# servo_header_board.net
KiCad netlist of a schematic drawn in Altium Designer
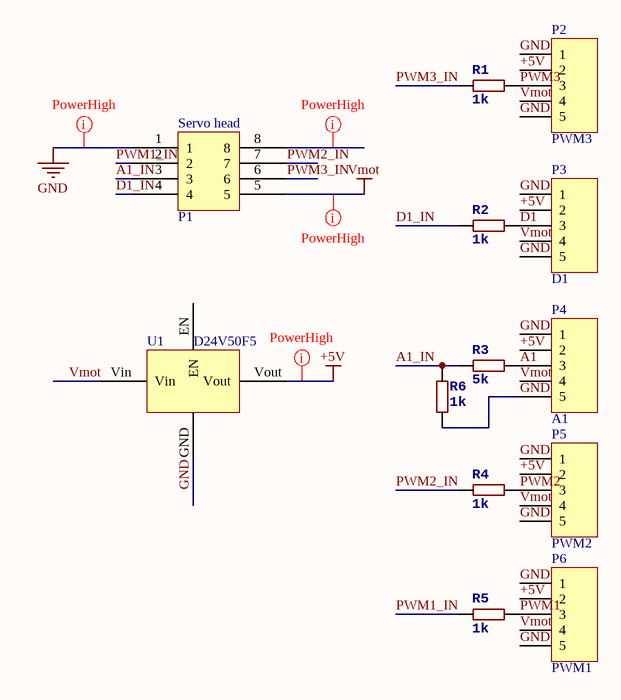
[diagram p0: servo_header_board.SchDoc]

(export (version "E")
  (design (tool "Eeschema 10.0.6"))
  (components
    (comp (ref "P1")
      (value "Servo head")
      (footprint "HOUSED8")
      (libsource (lib "myParts") (part "PIN_HOUSED_8"))
    )
    (comp (ref "P2")
      (value "PWM3")
      (footprint "HDR1X5")
      (description "Header, 5-Pin")
      (fields (field (name "PUBLISHER") "Altium Limited"))
      (libsource (lib "Miscellaneous Connectors") (part "Header 5"))
    )
    (comp (ref "P3")
      (value "D1")
      (footprint "HDR1X5")
      (description "Header, 5-Pin")
      (fields (field (name "PUBLISHER") "Altium Limited"))
      (libsource (lib "Miscellaneous Connectors") (part "Header 5"))
    )
    (comp (ref "P4")
      (value "A1")
      (footprint "HDR1X5")
      (description "Header, 5-Pin")
      (fields (field (name "PUBLISHER") "Altium Limited"))
      (libsource (lib "Miscellaneous Connectors") (part "Header 5"))
    )
    (comp (ref "P5")
      (value "PWM2")
      (footprint "HDR1X5")
      (description "Header, 5-Pin")
      (fields (field (name "PUBLISHER") "Altium Limited"))
      (libsource (lib "Miscellaneous Connectors") (part "Header 5"))
    )
    (comp (ref "P6")
      (value "PWM1")
      (footprint "HDR1X5")
      (description "Header, 5-Pin")
      (fields (field (name "PUBLISHER") "Altium Limited"))
      (libsource (lib "Miscellaneous Connectors") (part "Header 5"))
    )
    (comp (ref "R1")
      (value "1k")
      (footprint "R0805")
      (description "RESISTOR, European symbol")
      (libsource (lib "rcl") (part "R-EU"))
    )
    (comp (ref "R2")
      (value "1k")
      (footprint "R0805")
      (description "RESISTOR, European symbol")
      (libsource (lib "rcl") (part "R-EU"))
    )
    (comp (ref "R3")
      (value "5k")
      (footprint "R0805")
      (description "RESISTOR, European symbol")
      (libsource (lib "rcl") (part "R-EU"))
    )
    (comp (ref "R4")
      (value "1k")
      (footprint "R0805")
      (description "RESISTOR, European symbol")
      (libsource (lib "rcl") (part "R-EU"))
    )
    (comp (ref "R5")
      (value "1k")
      (footprint "R0805")
      (description "RESISTOR, European symbol")
      (libsource (lib "rcl") (part "R-EU"))
    )
    (comp (ref "R6")
      (value "1k")
      (footprint "R0805")
      (description "RESISTOR, European symbol")
      (libsource (lib "rcl") (part "R-EU"))
    )
    (comp (ref "U1")
      (value "D24V50F5")
      (footprint "D24V50F5-hori")
      (description "Pololu 5V, 5A Step-Down Voltage Regulator")
      (libsource (lib "myParts") (part "D24V50F5"))
    )
  )
  (nets
    (net (code "1") (name "+5V") (class "Default")
      (node (ref "P2") (pin "2") (pinfunction "2_2") (pintype "passive"))
      (node (ref "P3") (pin "2") (pinfunction "2_2") (pintype "passive"))
      (node (ref "P4") (pin "2") (pinfunction "2_2") (pintype "passive"))
      (node (ref "P5") (pin "2") (pinfunction "2_2") (pintype "passive"))
      (node (ref "P6") (pin "2") (pinfunction "2_2") (pintype "passive"))
      (node (ref "U1") (pin "Vout") (pinfunction "Vout_Vout") (pintype "power_in"))
    )
    (net (code "2") (name "/A1") (class "Default")
      (node (ref "P4") (pin "3") (pinfunction "3_3") (pintype "passive"))
      (node (ref "R3") (pin "2") (pinfunction "2_2") (pintype "passive"))
    )
    (net (code "3") (name "/A1_IN") (class "Default")
      (node (ref "P1") (pin "3") (pinfunction "3_3") (pintype "passive"))
      (node (ref "R3") (pin "1") (pinfunction "1_1") (pintype "passive"))
      (node (ref "R6") (pin "2") (pinfunction "2_2") (pintype "passive"))
    )
    (net (code "4") (name "/D1") (class "Default")
      (node (ref "P3") (pin "3") (pinfunction "3_3") (pintype "passive"))
      (node (ref "R2") (pin "2") (pinfunction "2_2") (pintype "passive"))
    )
    (net (code "5") (name "/D1_IN") (class "Default")
      (node (ref "P1") (pin "4") (pinfunction "4_4") (pintype "passive"))
      (node (ref "R2") (pin "1") (pinfunction "1_1") (pintype "passive"))
    )
    (net (code "6") (name "/PWM1") (class "Default")
      (node (ref "P6") (pin "3") (pinfunction "3_3") (pintype "passive"))
      (node (ref "R5") (pin "2") (pinfunction "2_2") (pintype "passive"))
    )
    (net (code "7") (name "/PWM1_IN") (class "Default")
      (node (ref "P1") (pin "2") (pinfunction "2_2") (pintype "passive"))
      (node (ref "R5") (pin "1") (pinfunction "1_1") (pintype "passive"))
    )
    (net (code "8") (name "/PWM2") (class "Default")
      (node (ref "P5") (pin "3") (pinfunction "3_3") (pintype "passive"))
      (node (ref "R4") (pin "2") (pinfunction "2_2") (pintype "passive"))
    )
    (net (code "9") (name "/PWM2_IN") (class "Default")
      (node (ref "P1") (pin "7") (pinfunction "7_7") (pintype "passive"))
      (node (ref "R4") (pin "1") (pinfunction "1_1") (pintype "passive"))
    )
    (net (code "10") (name "/PWM3") (class "Default")
      (node (ref "P2") (pin "3") (pinfunction "3_3") (pintype "passive"))
      (node (ref "R1") (pin "2") (pinfunction "2_2") (pintype "passive"))
    )
    (net (code "11") (name "/PWM3_IN") (class "Default")
      (node (ref "P1") (pin "6") (pinfunction "6_6") (pintype "passive"))
      (node (ref "R1") (pin "1") (pinfunction "1_1") (pintype "passive"))
    )
    (net (code "12") (name "GND") (class "Default")
      (node (ref "P1") (pin "1") (pinfunction "1_1") (pintype "passive"))
      (node (ref "P2") (pin "1") (pinfunction "1_1") (pintype "passive"))
      (node (ref "P2") (pin "5") (pinfunction "5_5") (pintype "passive"))
      (node (ref "P3") (pin "1") (pinfunction "1_1") (pintype "passive"))
      (node (ref "P3") (pin "5") (pinfunction "5_5") (pintype "passive"))
      (node (ref "P4") (pin "1") (pinfunction "1_1") (pintype "passive"))
      (node (ref "P4") (pin "5") (pinfunction "5_5") (pintype "passive"))
      (node (ref "P5") (pin "1") (pinfunction "1_1") (pintype "passive"))
      (node (ref "P5") (pin "5") (pinfunction "5_5") (pintype "passive"))
      (node (ref "P6") (pin "1") (pinfunction "1_1") (pintype "passive"))
      (node (ref "P6") (pin "5") (pinfunction "5_5") (pintype "passive"))
      (node (ref "R6") (pin "1") (pinfunction "1_1") (pintype "passive"))
      (node (ref "U1") (pin "GND") (pinfunction "GND_GND") (pintype "power_in"))
    )
    (net (code "13") (name "Vmot") (class "Default")
      (node (ref "P1") (pin "5") (pinfunction "5_5") (pintype "passive"))
      (node (ref "P2") (pin "4") (pinfunction "4_4") (pintype "passive"))
      (node (ref "P3") (pin "4") (pinfunction "4_4") (pintype "passive"))
      (node (ref "P4") (pin "4") (pinfunction "4_4") (pintype "passive"))
      (node (ref "P5") (pin "4") (pinfunction "4_4") (pintype "passive"))
      (node (ref "P6") (pin "4") (pinfunction "4_4") (pintype "passive"))
      (node (ref "U1") (pin "Vin") (pinfunction "Vin_Vin") (pintype "power_in"))
    )
    (net (code "14") (name "unconnected-(P1-Pad8)") (class "Default")
      (node (ref "P1") (pin "8") (pinfunction "8_8") (pintype "passive"))
    )
    (net (code "15") (name "unconnected-(U1-PadEN)") (class "Default")
      (node (ref "U1") (pin "EN") (pinfunction "EN_EN") (pintype "passive"))
    )
  )
)
